# ARDevelopmentPlat.net
KiCad netlist of a schematic drawn in Altium Designer
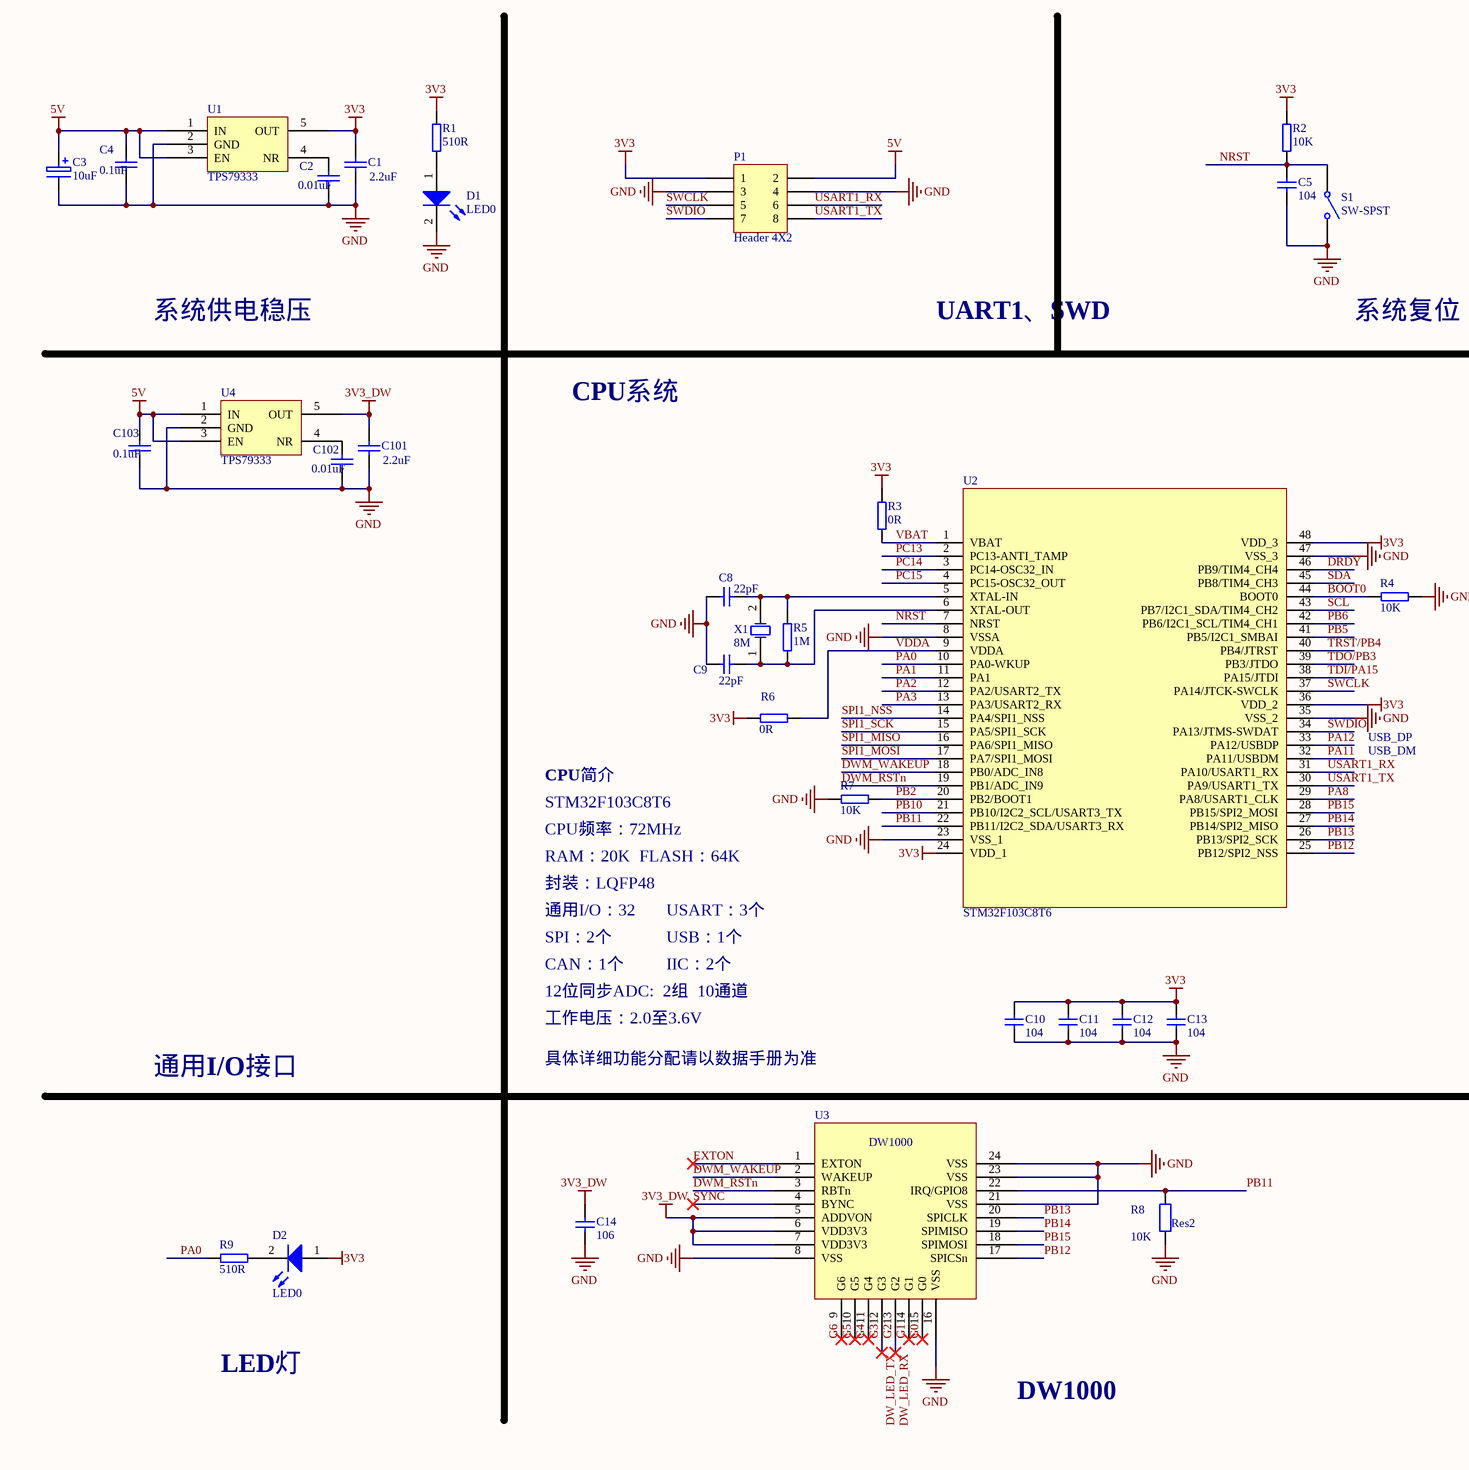
[diagram p0: ARDevelopmentPlat.SchDoc, left]
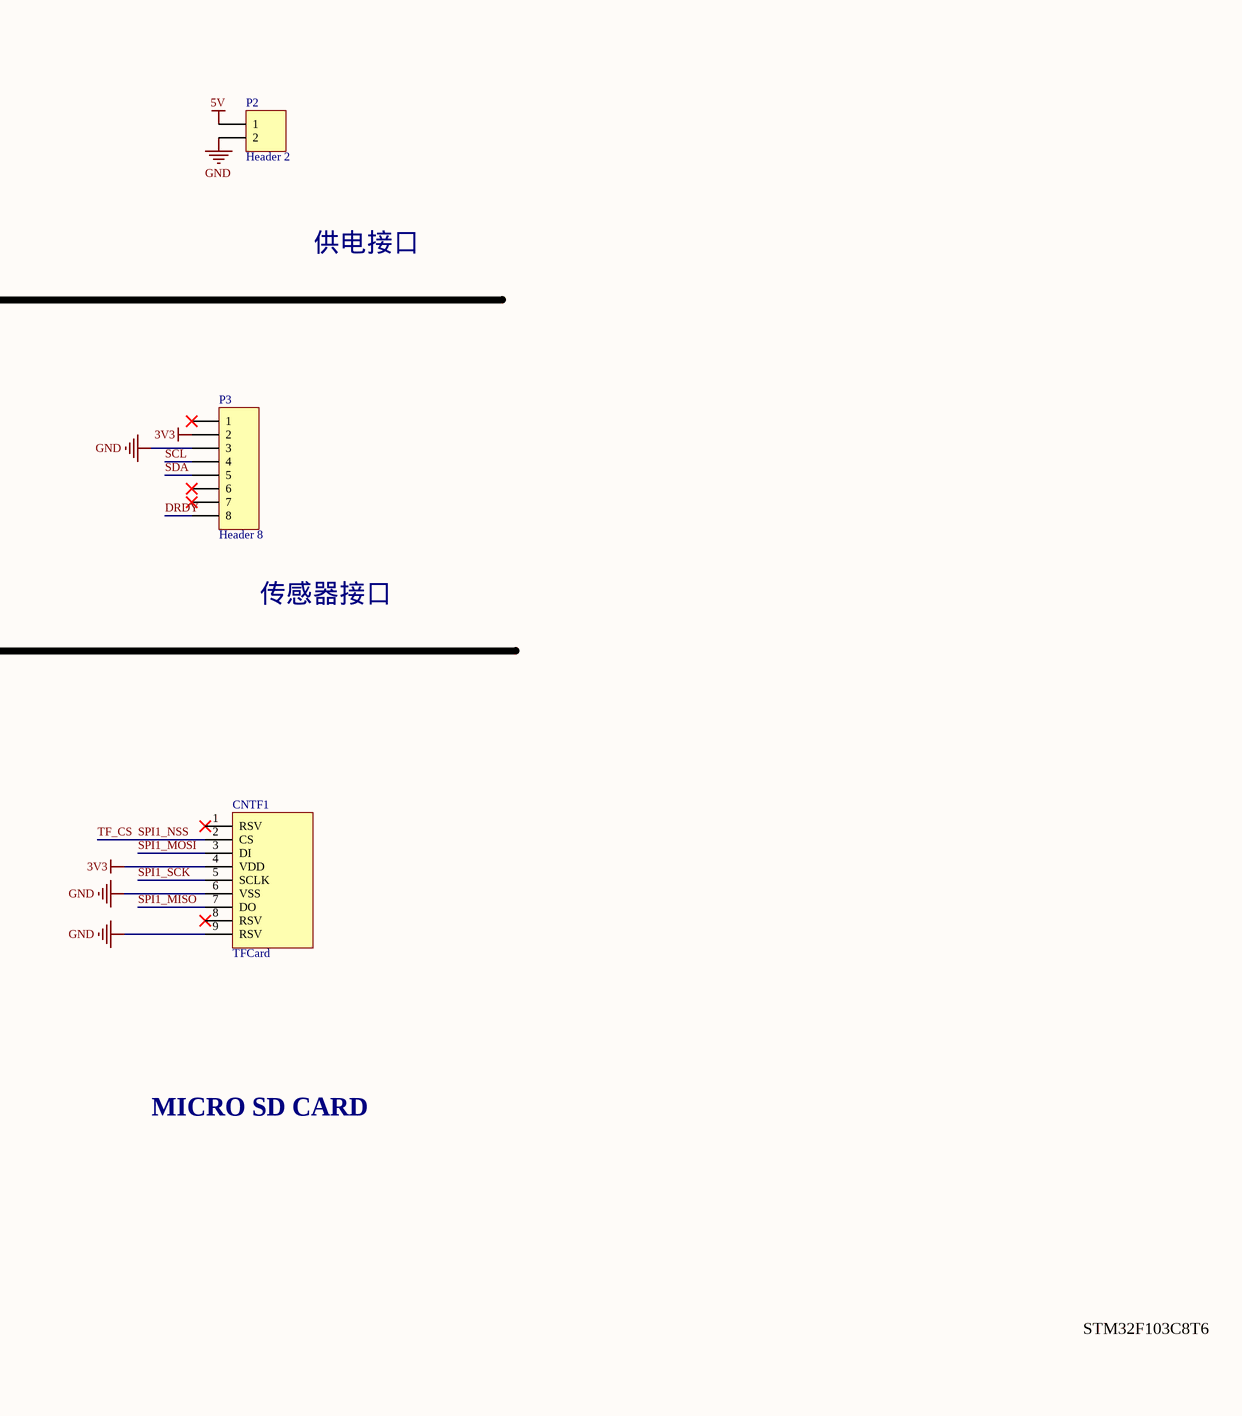
[diagram p1: ARDevelopmentPlat.SchDoc, right]

(export (version "E")
  (design (tool "Eeschema 10.0.6"))
  (components
    (comp (ref "C1")
      (value "2.2uF")
      (footprint "RC0603")
      (description "Capacitor")
      (fields (field (name "Comment") "Cap") (field (name "PUBLISHER") "Altium Limited"))
      (libsource (lib "Miscellaneous Devices") (part "Cap"))
    )
    (comp (ref "C2")
      (value "0.01uF")
      (footprint "RC0603")
      (description "Capacitor")
      (fields (field (name "Comment") "Cap") (field (name "PUBLISHER") "Altium Limited"))
      (libsource (lib "Miscellaneous Devices") (part "Cap"))
    )
    (comp (ref "C3")
      (value "10uF")
      (footprint "RC0805")
      (description "Electrolytic Capacitor")
      (libsource (lib "Schlib1") (part "cap_polarity2"))
    )
    (comp (ref "C4")
      (value "0.1uF")
      (footprint "RC0603")
      (description "Capacitor")
      (fields (field (name "Comment") "Cap") (field (name "PUBLISHER") "Altium Limited"))
      (libsource (lib "Miscellaneous Devices") (part "Cap"))
    )
    (comp (ref "C5")
      (value "104")
      (footprint "RC0603")
      (description "Capacitor")
      (fields (field (name "PUBLISHER") "ZL_A0OFFICE"))
      (libsource (lib "CommomDevices") (part "CAP1"))
    )
    (comp (ref "C8")
      (value "22pF")
      (footprint "RC0603")
      (description "Capacitor")
      (fields (field (name "PUBLISHER") "ZL_A0OFFICE"))
      (libsource (lib "CommomDevices") (part "CAP1"))
    )
    (comp (ref "C9")
      (value "22pF")
      (footprint "RC0603")
      (description "Capacitor")
      (fields (field (name "PUBLISHER") "ZL_A0OFFICE"))
      (libsource (lib "CommomDevices") (part "CAP1"))
    )
    (comp (ref "C10")
      (value "104")
      (footprint "RC0603")
      (description "Capacitor")
      (fields (field (name "PUBLISHER") "ZL_A0OFFICE"))
      (libsource (lib "CommomDevices") (part "CAP1"))
    )
    (comp (ref "C11")
      (value "104")
      (footprint "RC0603")
      (description "Capacitor")
      (fields (field (name "PUBLISHER") "ZL_A0OFFICE"))
      (libsource (lib "CommomDevices") (part "CAP1"))
    )
    (comp (ref "C12")
      (value "104")
      (footprint "RC0603")
      (description "Capacitor")
      (fields (field (name "PUBLISHER") "ZL_A0OFFICE"))
      (libsource (lib "CommomDevices") (part "CAP1"))
    )
    (comp (ref "C13")
      (value "104")
      (footprint "RC0603")
      (description "Capacitor")
      (fields (field (name "PUBLISHER") "ZL_A0OFFICE"))
      (libsource (lib "CommomDevices") (part "CAP1"))
    )
    (comp (ref "C14")
      (value "106")
      (footprint "RC0805")
      (description "Capacitor")
      (fields (field (name "PUBLISHER") "ZL_A0OFFICE"))
      (libsource (lib "CommomDevices") (part "CAP1"))
    )
    (comp (ref "C101")
      (value "2.2uF")
      (footprint "RC0603")
      (description "Capacitor")
      (fields (field (name "Comment") "Cap") (field (name "PUBLISHER") "Altium Limited"))
      (libsource (lib "Miscellaneous Devices") (part "Cap"))
    )
    (comp (ref "C102")
      (value "0.01uF")
      (footprint "RC0603")
      (description "Capacitor")
      (fields (field (name "Comment") "Cap") (field (name "PUBLISHER") "Altium Limited"))
      (libsource (lib "Miscellaneous Devices") (part "Cap"))
    )
    (comp (ref "C103")
      (value "0.1uF")
      (footprint "RC0603")
      (description "Capacitor")
      (fields (field (name "Comment") "Cap") (field (name "PUBLISHER") "Altium Limited"))
      (libsource (lib "Miscellaneous Devices") (part "Cap"))
    )
    (comp (ref "CNTF1")
      (value "TFCard")
      (footprint "MICRO SD")
      (libsource (lib "ARDevelopmentPlat") (part "TFCard"))
    )
    (comp (ref "D1")
      (value "LED0")
      (footprint "LED0805")
      (description "Typical INFRARED GaAs LED")
      (libsource (lib "Miscellaneous Devices") (part "LED0"))
    )
    (comp (ref "D2")
      (value "LED0")
      (footprint "LED0805")
      (description "Typical INFRARED GaAs LED")
      (libsource (lib "Miscellaneous Devices") (part "LED0"))
    )
    (comp (ref "P1")
      (value "Header 4X2")
      (footprint "HDR2X4")
      (description "Header, 4-Pin, Dual row")
      (fields (field (name "PUBLISHER") "Altium Limited"))
      (libsource (lib "Miscellaneous Connectors") (part "Header 4X2"))
    )
    (comp (ref "P2")
      (value "Header 2")
      (footprint "HDR1X2")
      (description "Header, 2-Pin")
      (fields (field (name "PUBLISHER") "Altium Limited"))
      (libsource (lib "Miscellaneous Connectors") (part "Header 2"))
    )
    (comp (ref "P3")
      (value "Header 8")
      (footprint "HDR1X8")
      (description "Header, 8-Pin")
      (fields (field (name "PUBLISHER") "Altium Limited"))
      (libsource (lib "Miscellaneous Connectors") (part "Header 8"))
    )
    (comp (ref "R1") (value "510R") (footprint "RC0603") (libsource (lib "ZIBO V2.0_Main") (part "R")))
    (comp (ref "R2") (value "10K") (footprint "RC0603") (libsource (lib "ZIBO V2.0_Main") (part "R")))
    (comp (ref "R3") (value "0R") (footprint "RC0603") (libsource (lib "ZIBO V2.0_Main") (part "R")))
    (comp (ref "R4") (value "10K") (footprint "RC0603") (libsource (lib "ZIBO V2.0_Main") (part "R")))
    (comp (ref "R5") (value "1M") (footprint "RC0603") (libsource (lib "ZIBO V2.0_Main") (part "R")))
    (comp (ref "R6") (value "0R") (footprint "RC0603") (libsource (lib "ZIBO V2.0_Main") (part "R")))
    (comp (ref "R7") (value "10K") (footprint "RC0603") (libsource (lib "ZIBO V2.0_Main") (part "R")))
    (comp (ref "R8")
      (value "Res2")
      (footprint "RC0603")
      (description "Resistor")
      (fields (field (name "ALTIUM_VALUE") "10K") (field (name "PUBLISHER") "Altium Limited"))
      (libsource (lib "Miscellaneous Devices") (part "Res2"))
    )
    (comp (ref "R9") (value "510R") (footprint "RC0603") (libsource (lib "ZIBO V2.0_Main") (part "R")))
    (comp (ref "S1")
      (value "SW-SPST")
      (footprint "SMT-KEY")
      (description "Single-Pole, Single-Throw Switch")
      (libsource (lib "Miscellaneous Devices") (part "SW-SPST"))
    )
    (comp (ref "U1") (value "TPS79333") (footprint "SOT-23-5") (libsource (lib "STM32_1") (part "TPS79333")))
    (comp (ref "U2")
      (value "STM32F103C8T6")
      (footprint "LQFP48")
      (libsource (lib "STM32_Smart") (part "STM32F103C8T6"))
    )
    (comp (ref "U3")
      (value "DW1000")
      (footprint "ARDevelopmentPlat:DWM1000")
      (libsource (lib "Schlib1") (part "DW1000"))
    )
    (comp (ref "U4") (value "TPS79333") (footprint "SOT-23-5") (libsource (lib "STM32_1") (part "TPS79333")))
    (comp (ref "X1")
      (value "8M")
      (footprint "SMD5032")
      (description "Crystal Oscillator")
      (fields (field (name "PUBLISHER") "ZL_A0OFFICE"))
      (libsource (lib "CommomDevices") (part "XTAL_SMD"))
    )
  )
  (nets
    (net (code "1") (name "/BOOT0") (class "Default")
      (node (ref "R4") (pin "2") (pinfunction "2_2") (pintype "passive"))
      (node (ref "U2") (pin "44") (pinfunction "BOOT0_44") (pintype "passive"))
    )
    (net (code "2") (name "/DRDY") (class "Default")
      (node (ref "P3") (pin "8") (pinfunction "8_8") (pintype "passive"))
      (node (ref "U2") (pin "46") (pinfunction "PB9/TIM4_CH4_46") (pintype "passive"))
    )
    (net (code "3") (name "/DWM_RSTn") (class "Default")
      (node (ref "U2") (pin "19") (pinfunction "PB1/ADC_IN9_19") (pintype "passive"))
      (node (ref "U3") (pin "3") (pinfunction "RBTn_3") (pintype "passive"))
    )
    (net (code "4") (name "/DWM_WAKEUP") (class "Default")
      (node (ref "U2") (pin "18") (pinfunction "PB0/ADC_IN8_18") (pintype "passive"))
      (node (ref "U3") (pin "2") (pinfunction "WAKEUP_2") (pintype "passive"))
    )
    (net (code "5") (name "/DW_LED_RX") (class "Default")
      (node (ref "U3") (pin "13") (pinfunction "G2_13") (pintype "passive+no_connect"))
    )
    (net (code "6") (name "/DW_LED_TX") (class "Default")
      (node (ref "U3") (pin "12") (pinfunction "G3_12") (pintype "passive+no_connect"))
    )
    (net (code "7") (name "/EXTON") (class "Default")
      (node (ref "U3") (pin "1") (pinfunction "EXTON_1") (pintype "passive+no_connect"))
    )
    (net (code "8") (name "/G0") (class "Default")
      (node (ref "U3") (pin "15") (pinfunction "G0_15") (pintype "passive+no_connect"))
    )
    (net (code "9") (name "/G1") (class "Default")
      (node (ref "U3") (pin "14") (pinfunction "G1_14") (pintype "passive+no_connect"))
    )
    (net (code "10") (name "/G4") (class "Default")
      (node (ref "U3") (pin "11") (pinfunction "G4_11") (pintype "passive+no_connect"))
    )
    (net (code "11") (name "/G5") (class "Default")
      (node (ref "U3") (pin "10") (pinfunction "G5_10") (pintype "passive+no_connect"))
    )
    (net (code "12") (name "/G6") (class "Default")
      (node (ref "U3") (pin "9") (pinfunction "G6_9") (pintype "passive+no_connect"))
    )
    (net (code "13") (name "/NRST") (class "Default")
      (node (ref "C5") (pin "1") (pinfunction "1_1") (pintype "passive"))
      (node (ref "R2") (pin "1") (pinfunction "1_1") (pintype "passive"))
      (node (ref "S1") (pin "1") (pinfunction "COMMON_1") (pintype "passive"))
      (node (ref "U2") (pin "7") (pinfunction "NRST_7") (pintype "passive"))
    )
    (net (code "14") (name "/PA0") (class "Default")
      (node (ref "R9") (pin "1") (pinfunction "1_1") (pintype "passive"))
      (node (ref "U2") (pin "10") (pinfunction "PA0-WKUP_10") (pintype "passive"))
    )
    (net (code "15") (name "/PA1") (class "Default")
      (node (ref "U2") (pin "11") (pinfunction "PA1_11") (pintype "passive"))
    )
    (net (code "16") (name "/PA2") (class "Default")
      (node (ref "U2") (pin "12") (pinfunction "PA2/USART2_TX_12") (pintype "passive"))
    )
    (net (code "17") (name "/PA3") (class "Default")
      (node (ref "U2") (pin "13") (pinfunction "PA3/USART2_RX_13") (pintype "passive"))
    )
    (net (code "18") (name "/PA8") (class "Default")
      (node (ref "U2") (pin "29") (pinfunction "PA8/USART1_CLK_29") (pintype "passive"))
    )
    (net (code "19") (name "/PA11") (class "Default")
      (node (ref "U2") (pin "32") (pinfunction "PA11/USBDM_32") (pintype "passive"))
    )
    (net (code "20") (name "/PA12") (class "Default")
      (node (ref "U2") (pin "33") (pinfunction "PA12/USBDP_33") (pintype "passive"))
    )
    (net (code "21") (name "/PB2") (class "Default")
      (node (ref "R7") (pin "1") (pinfunction "1_1") (pintype "passive"))
      (node (ref "U2") (pin "20") (pinfunction "PB2/BOOT1_20") (pintype "passive"))
    )
    (net (code "22") (name "/PB5") (class "Default")
      (node (ref "U2") (pin "41") (pinfunction "PB5/I2C1_SMBAI_41") (pintype "passive"))
    )
    (net (code "23") (name "/PB6") (class "Default")
      (node (ref "U2") (pin "42") (pinfunction "PB6/I2C1_SCL/TIM4_CH1_42") (pintype "passive"))
    )
    (net (code "24") (name "/PB10") (class "Default")
      (node (ref "U2") (pin "21") (pinfunction "PB10/I2C2_SCL/USART3_TX_21") (pintype "passive"))
    )
    (net (code "25") (name "/PB11") (class "Default")
      (node (ref "R8") (pin "2") (pinfunction "2_2") (pintype "passive"))
      (node (ref "U2") (pin "22") (pinfunction "PB11/I2C2_SDA/USART3_RX_22") (pintype "passive"))
      (node (ref "U3") (pin "22") (pinfunction "IRQ/GPIO8_22") (pintype "passive"))
    )
    (net (code "26") (name "/PB12") (class "Default")
      (node (ref "U2") (pin "25") (pinfunction "PB12/SPI2_NSS_25") (pintype "passive"))
      (node (ref "U3") (pin "17") (pinfunction "SPICSn_17") (pintype "passive"))
    )
    (net (code "27") (name "/PB13") (class "Default")
      (node (ref "U2") (pin "26") (pinfunction "PB13/SPI2_SCK_26") (pintype "passive"))
      (node (ref "U3") (pin "20") (pinfunction "SPICLK_20") (pintype "passive"))
    )
    (net (code "28") (name "/PB14") (class "Default")
      (node (ref "U2") (pin "27") (pinfunction "PB14/SPI2_MISO_27") (pintype "passive"))
      (node (ref "U3") (pin "19") (pinfunction "SPIMISO_19") (pintype "passive"))
    )
    (net (code "29") (name "/PB15") (class "Default")
      (node (ref "U2") (pin "28") (pinfunction "PB15/SPI2_MOSI_28") (pintype "passive"))
      (node (ref "U3") (pin "18") (pinfunction "SPIMOSI_18") (pintype "passive"))
    )
    (net (code "30") (name "/PC13") (class "Default")
      (node (ref "U2") (pin "2") (pinfunction "PC13-ANTI_TAMP_2") (pintype "passive"))
    )
    (net (code "31") (name "/PC14") (class "Default")
      (node (ref "U2") (pin "3") (pinfunction "PC14-OSC32_IN_3") (pintype "passive"))
    )
    (net (code "32") (name "/PC15") (class "Default")
      (node (ref "U2") (pin "4") (pinfunction "PC15-OSC32_OUT_4") (pintype "passive"))
    )
    (net (code "33") (name "/SCL") (class "Default")
      (node (ref "P3") (pin "4") (pinfunction "4_4") (pintype "passive"))
      (node (ref "U2") (pin "43") (pinfunction "PB7/I2C1_SDA/TIM4_CH2_43") (pintype "passive"))
    )
    (net (code "34") (name "/SDA") (class "Default")
      (node (ref "P3") (pin "5") (pinfunction "5_5") (pintype "passive"))
      (node (ref "U2") (pin "45") (pinfunction "PB8/TIM4_CH3_45") (pintype "passive"))
    )
    (net (code "35") (name "/SPI1_MISO") (class "Default")
      (node (ref "CNTF1") (pin "7") (pinfunction "DO_7") (pintype "passive"))
      (node (ref "U2") (pin "16") (pinfunction "PA6/SPI1_MISO_16") (pintype "passive"))
    )
    (net (code "36") (name "/SPI1_MOSI") (class "Default")
      (node (ref "CNTF1") (pin "3") (pinfunction "DI_3") (pintype "passive"))
      (node (ref "U2") (pin "17") (pinfunction "PA7/SPI1_MOSI_17") (pintype "passive"))
    )
    (net (code "37") (name "/SPI1_NSS") (class "Default")
      (node (ref "CNTF1") (pin "2") (pinfunction "CS_2") (pintype "passive"))
      (node (ref "U2") (pin "14") (pinfunction "PA4/SPI1_NSS_14") (pintype "passive"))
    )
    (net (code "38") (name "/SPI1_SCK") (class "Default")
      (node (ref "CNTF1") (pin "5") (pinfunction "SCLK_5") (pintype "passive"))
      (node (ref "U2") (pin "15") (pinfunction "PA5/SPI1_SCK_15") (pintype "passive"))
    )
    (net (code "39") (name "/SWCLK") (class "Default")
      (node (ref "P1") (pin "5") (pinfunction "5_5") (pintype "passive"))
      (node (ref "U2") (pin "37") (pinfunction "PA14/JTCK-SWCLK_37") (pintype "passive"))
    )
    (net (code "40") (name "/SWDIO") (class "Default")
      (node (ref "P1") (pin "7") (pinfunction "7_7") (pintype "passive"))
      (node (ref "U2") (pin "34") (pinfunction "PA13/JTMS-SWDAT_34") (pintype "passive"))
    )
    (net (code "41") (name "/SYNC") (class "Default")
      (node (ref "U3") (pin "4") (pinfunction "BYNC_4") (pintype "passive+no_connect"))
    )
    (net (code "42") (name "/TDI{slash}PA15") (class "Default")
      (node (ref "U2") (pin "38") (pinfunction "PA15/JTDI_38") (pintype "passive"))
    )
    (net (code "43") (name "/TDO{slash}PB3") (class "Default")
      (node (ref "U2") (pin "39") (pinfunction "PB3/JTDO_39") (pintype "passive"))
    )
    (net (code "44") (name "/TRST{slash}PB4") (class "Default")
      (node (ref "U2") (pin "40") (pinfunction "PB4/JTRST_40") (pintype "passive"))
    )
    (net (code "45") (name "/USART1_RX") (class "Default")
      (node (ref "P1") (pin "6") (pinfunction "6_6") (pintype "passive"))
      (node (ref "U2") (pin "31") (pinfunction "PA10/USART1_RX_31") (pintype "passive"))
    )
    (net (code "46") (name "/USART1_TX") (class "Default")
      (node (ref "P1") (pin "8") (pinfunction "8_8") (pintype "passive"))
      (node (ref "U2") (pin "30") (pinfunction "PA9/USART1_TX_30") (pintype "passive"))
    )
    (net (code "47") (name "/VBAT") (class "Default")
      (node (ref "R3") (pin "1") (pinfunction "1_1") (pintype "passive"))
      (node (ref "U2") (pin "1") (pinfunction "VBAT_1") (pintype "passive"))
    )
    (net (code "48") (name "/VDDA") (class "Default")
      (node (ref "R6") (pin "1") (pinfunction "1_1") (pintype "passive"))
      (node (ref "U2") (pin "9") (pinfunction "VDDA_9") (pintype "passive"))
    )
    (net (code "49") (name "3V3") (class "Default")
      (node (ref "C1") (pin "2") (pinfunction "2_2") (pintype "passive"))
      (node (ref "C10") (pin "1") (pinfunction "1_1") (pintype "passive"))
      (node (ref "C11") (pin "1") (pinfunction "1_1") (pintype "passive"))
      (node (ref "C12") (pin "1") (pinfunction "1_1") (pintype "passive"))
      (node (ref "C13") (pin "1") (pinfunction "1_1") (pintype "passive"))
      (node (ref "CNTF1") (pin "4") (pinfunction "VDD_4") (pintype "passive"))
      (node (ref "D2") (pin "1") (pinfunction "A_1") (pintype "passive"))
      (node (ref "P1") (pin "1") (pinfunction "1_1") (pintype "passive"))
      (node (ref "P3") (pin "2") (pinfunction "2_2") (pintype "passive"))
      (node (ref "R1") (pin "2") (pinfunction "2_2") (pintype "passive"))
      (node (ref "R2") (pin "2") (pinfunction "2_2") (pintype "passive"))
      (node (ref "R3") (pin "2") (pinfunction "2_2") (pintype "passive"))
      (node (ref "R6") (pin "2") (pinfunction "2_2") (pintype "passive"))
      (node (ref "U1") (pin "5") (pinfunction "OUT_5") (pintype "passive"))
      (node (ref "U2") (pin "24") (pinfunction "VDD_1_24") (pintype "passive"))
      (node (ref "U2") (pin "36") (pinfunction "VDD_2_36") (pintype "passive"))
      (node (ref "U2") (pin "48") (pinfunction "VDD_3_48") (pintype "passive"))
    )
    (net (code "50") (name "3V3_DW") (class "Default")
      (node (ref "C101") (pin "2") (pinfunction "2_2") (pintype "passive"))
      (node (ref "C14") (pin "1") (pinfunction "1_1") (pintype "passive"))
      (node (ref "U3") (pin "5") (pinfunction "ADDVON_5") (pintype "passive"))
      (node (ref "U3") (pin "6") (pinfunction "VDD3V3_6") (pintype "passive"))
      (node (ref "U3") (pin "7") (pinfunction "VDD3V3_7") (pintype "passive"))
      (node (ref "U4") (pin "5") (pinfunction "OUT_5") (pintype "passive"))
    )
    (net (code "51") (name "5V") (class "Default")
      (node (ref "C103") (pin "2") (pinfunction "2_2") (pintype "passive"))
      (node (ref "C3") (pin "1") (pinfunction "1_1") (pintype "passive"))
      (node (ref "C4") (pin "2") (pinfunction "2_2") (pintype "passive"))
      (node (ref "P1") (pin "2") (pinfunction "2_2") (pintype "passive"))
      (node (ref "P2") (pin "1") (pinfunction "1_1") (pintype "passive"))
      (node (ref "U1") (pin "1") (pinfunction "IN_1") (pintype "passive"))
      (node (ref "U1") (pin "3") (pinfunction "EN_3") (pintype "passive"))
      (node (ref "U4") (pin "1") (pinfunction "IN_1") (pintype "passive"))
      (node (ref "U4") (pin "3") (pinfunction "EN_3") (pintype "passive"))
    )
    (net (code "52") (name "GND") (class "Default")
      (node (ref "C1") (pin "1") (pinfunction "1_1") (pintype "passive"))
      (node (ref "C10") (pin "2") (pinfunction "2_2") (pintype "passive"))
      (node (ref "C101") (pin "1") (pinfunction "1_1") (pintype "passive"))
      (node (ref "C102") (pin "1") (pinfunction "1_1") (pintype "passive"))
      (node (ref "C103") (pin "1") (pinfunction "1_1") (pintype "passive"))
      (node (ref "C11") (pin "2") (pinfunction "2_2") (pintype "passive"))
      (node (ref "C12") (pin "2") (pinfunction "2_2") (pintype "passive"))
      (node (ref "C13") (pin "2") (pinfunction "2_2") (pintype "passive"))
      (node (ref "C14") (pin "2") (pinfunction "2_2") (pintype "passive"))
      (node (ref "C2") (pin "1") (pinfunction "1_1") (pintype "passive"))
      (node (ref "C3") (pin "2") (pinfunction "2_2") (pintype "passive"))
      (node (ref "C4") (pin "1") (pinfunction "1_1") (pintype "passive"))
      (node (ref "C5") (pin "2") (pinfunction "2_2") (pintype "passive"))
      (node (ref "C8") (pin "2") (pinfunction "2_2") (pintype "passive"))
      (node (ref "C9") (pin "2") (pinfunction "2_2") (pintype "passive"))
      (node (ref "CNTF1") (pin "6") (pinfunction "VSS_6") (pintype "passive"))
      (node (ref "CNTF1") (pin "9") (pinfunction "RSV_9") (pintype "passive"))
      (node (ref "D1") (pin "2") (pinfunction "K_2") (pintype "passive"))
      (node (ref "P1") (pin "3") (pinfunction "3_3") (pintype "passive"))
      (node (ref "P1") (pin "4") (pinfunction "4_4") (pintype "passive"))
      (node (ref "P2") (pin "2") (pinfunction "2_2") (pintype "passive"))
      (node (ref "P3") (pin "3") (pinfunction "3_3") (pintype "passive"))
      (node (ref "R4") (pin "1") (pinfunction "1_1") (pintype "passive"))
      (node (ref "R7") (pin "2") (pinfunction "2_2") (pintype "passive"))
      (node (ref "R8") (pin "1") (pinfunction "1_1") (pintype "passive"))
      (node (ref "S1") (pin "2") (pinfunction "NO_2") (pintype "passive"))
      (node (ref "U1") (pin "2") (pinfunction "GND_2") (pintype "passive"))
      (node (ref "U2") (pin "23") (pinfunction "VSS_1_23") (pintype "passive"))
      (node (ref "U2") (pin "35") (pinfunction "VSS_2_35") (pintype "passive"))
      (node (ref "U2") (pin "47") (pinfunction "VSS_3_47") (pintype "passive"))
      (node (ref "U2") (pin "8") (pinfunction "VSSA_8") (pintype "passive"))
      (node (ref "U3") (pin "16") (pinfunction "VSS_16") (pintype "passive"))
      (node (ref "U3") (pin "21") (pinfunction "VSS_21") (pintype "passive"))
      (node (ref "U3") (pin "23") (pinfunction "VSS_23") (pintype "passive"))
      (node (ref "U3") (pin "24") (pinfunction "VSS_24") (pintype "passive"))
      (node (ref "U3") (pin "8") (pinfunction "VSS_8") (pintype "passive"))
      (node (ref "U4") (pin "2") (pinfunction "GND_2") (pintype "passive"))
    )
    (net (code "53") (name "Net-(D1-A)") (class "Default")
      (node (ref "D1") (pin "1") (pinfunction "A_1") (pintype "passive"))
      (node (ref "R1") (pin "1") (pinfunction "1_1") (pintype "passive"))
    )
    (net (code "54") (name "Net-(D2-K)") (class "Default")
      (node (ref "D2") (pin "2") (pinfunction "K_2") (pintype "passive"))
      (node (ref "R9") (pin "2") (pinfunction "2_2") (pintype "passive"))
    )
    (net (code "55") (name "Net-(U1-NR)") (class "Default")
      (node (ref "C2") (pin "2") (pinfunction "2_2") (pintype "passive"))
      (node (ref "U1") (pin "4") (pinfunction "NR_4") (pintype "passive"))
    )
    (net (code "56") (name "Net-(U2-XTAL-IN)") (class "Default")
      (node (ref "C8") (pin "1") (pinfunction "1_1") (pintype "passive"))
      (node (ref "R5") (pin "2") (pinfunction "2_2") (pintype "passive"))
      (node (ref "U2") (pin "5") (pinfunction "XTAL-IN_5") (pintype "passive"))
      (node (ref "X1") (pin "2") (pinfunction "2_2") (pintype "passive"))
    )
    (net (code "57") (name "Net-(U2-XTAL-OUT)") (class "Default")
      (node (ref "C9") (pin "1") (pinfunction "1_1") (pintype "passive"))
      (node (ref "R5") (pin "1") (pinfunction "1_1") (pintype "passive"))
      (node (ref "U2") (pin "6") (pinfunction "XTAL-OUT_6") (pintype "passive"))
      (node (ref "X1") (pin "1") (pinfunction "1_1") (pintype "passive"))
    )
    (net (code "58") (name "Net-(U4-NR)") (class "Default")
      (node (ref "C102") (pin "2") (pinfunction "2_2") (pintype "passive"))
      (node (ref "U4") (pin "4") (pinfunction "NR_4") (pintype "passive"))
    )
    (net (code "59") (name "unconnected-(CNTF1-RSV-Pad1)") (class "Default")
      (node (ref "CNTF1") (pin "1") (pinfunction "RSV_1") (pintype "passive+no_connect"))
    )
    (net (code "60") (name "unconnected-(CNTF1-RSV-Pad8)") (class "Default")
      (node (ref "CNTF1") (pin "8") (pinfunction "RSV_8") (pintype "passive+no_connect"))
    )
    (net (code "61") (name "unconnected-(P3-Pad1)") (class "Default")
      (node (ref "P3") (pin "1") (pinfunction "1_1") (pintype "passive+no_connect"))
    )
    (net (code "62") (name "unconnected-(P3-Pad6)") (class "Default")
      (node (ref "P3") (pin "6") (pinfunction "6_6") (pintype "passive+no_connect"))
    )
    (net (code "63") (name "unconnected-(P3-Pad7)") (class "Default")
      (node (ref "P3") (pin "7") (pinfunction "7_7") (pintype "passive+no_connect"))
    )
  )
)
